# power_supply.net
KiCad netlist of a schematic drawn in Altium Designer
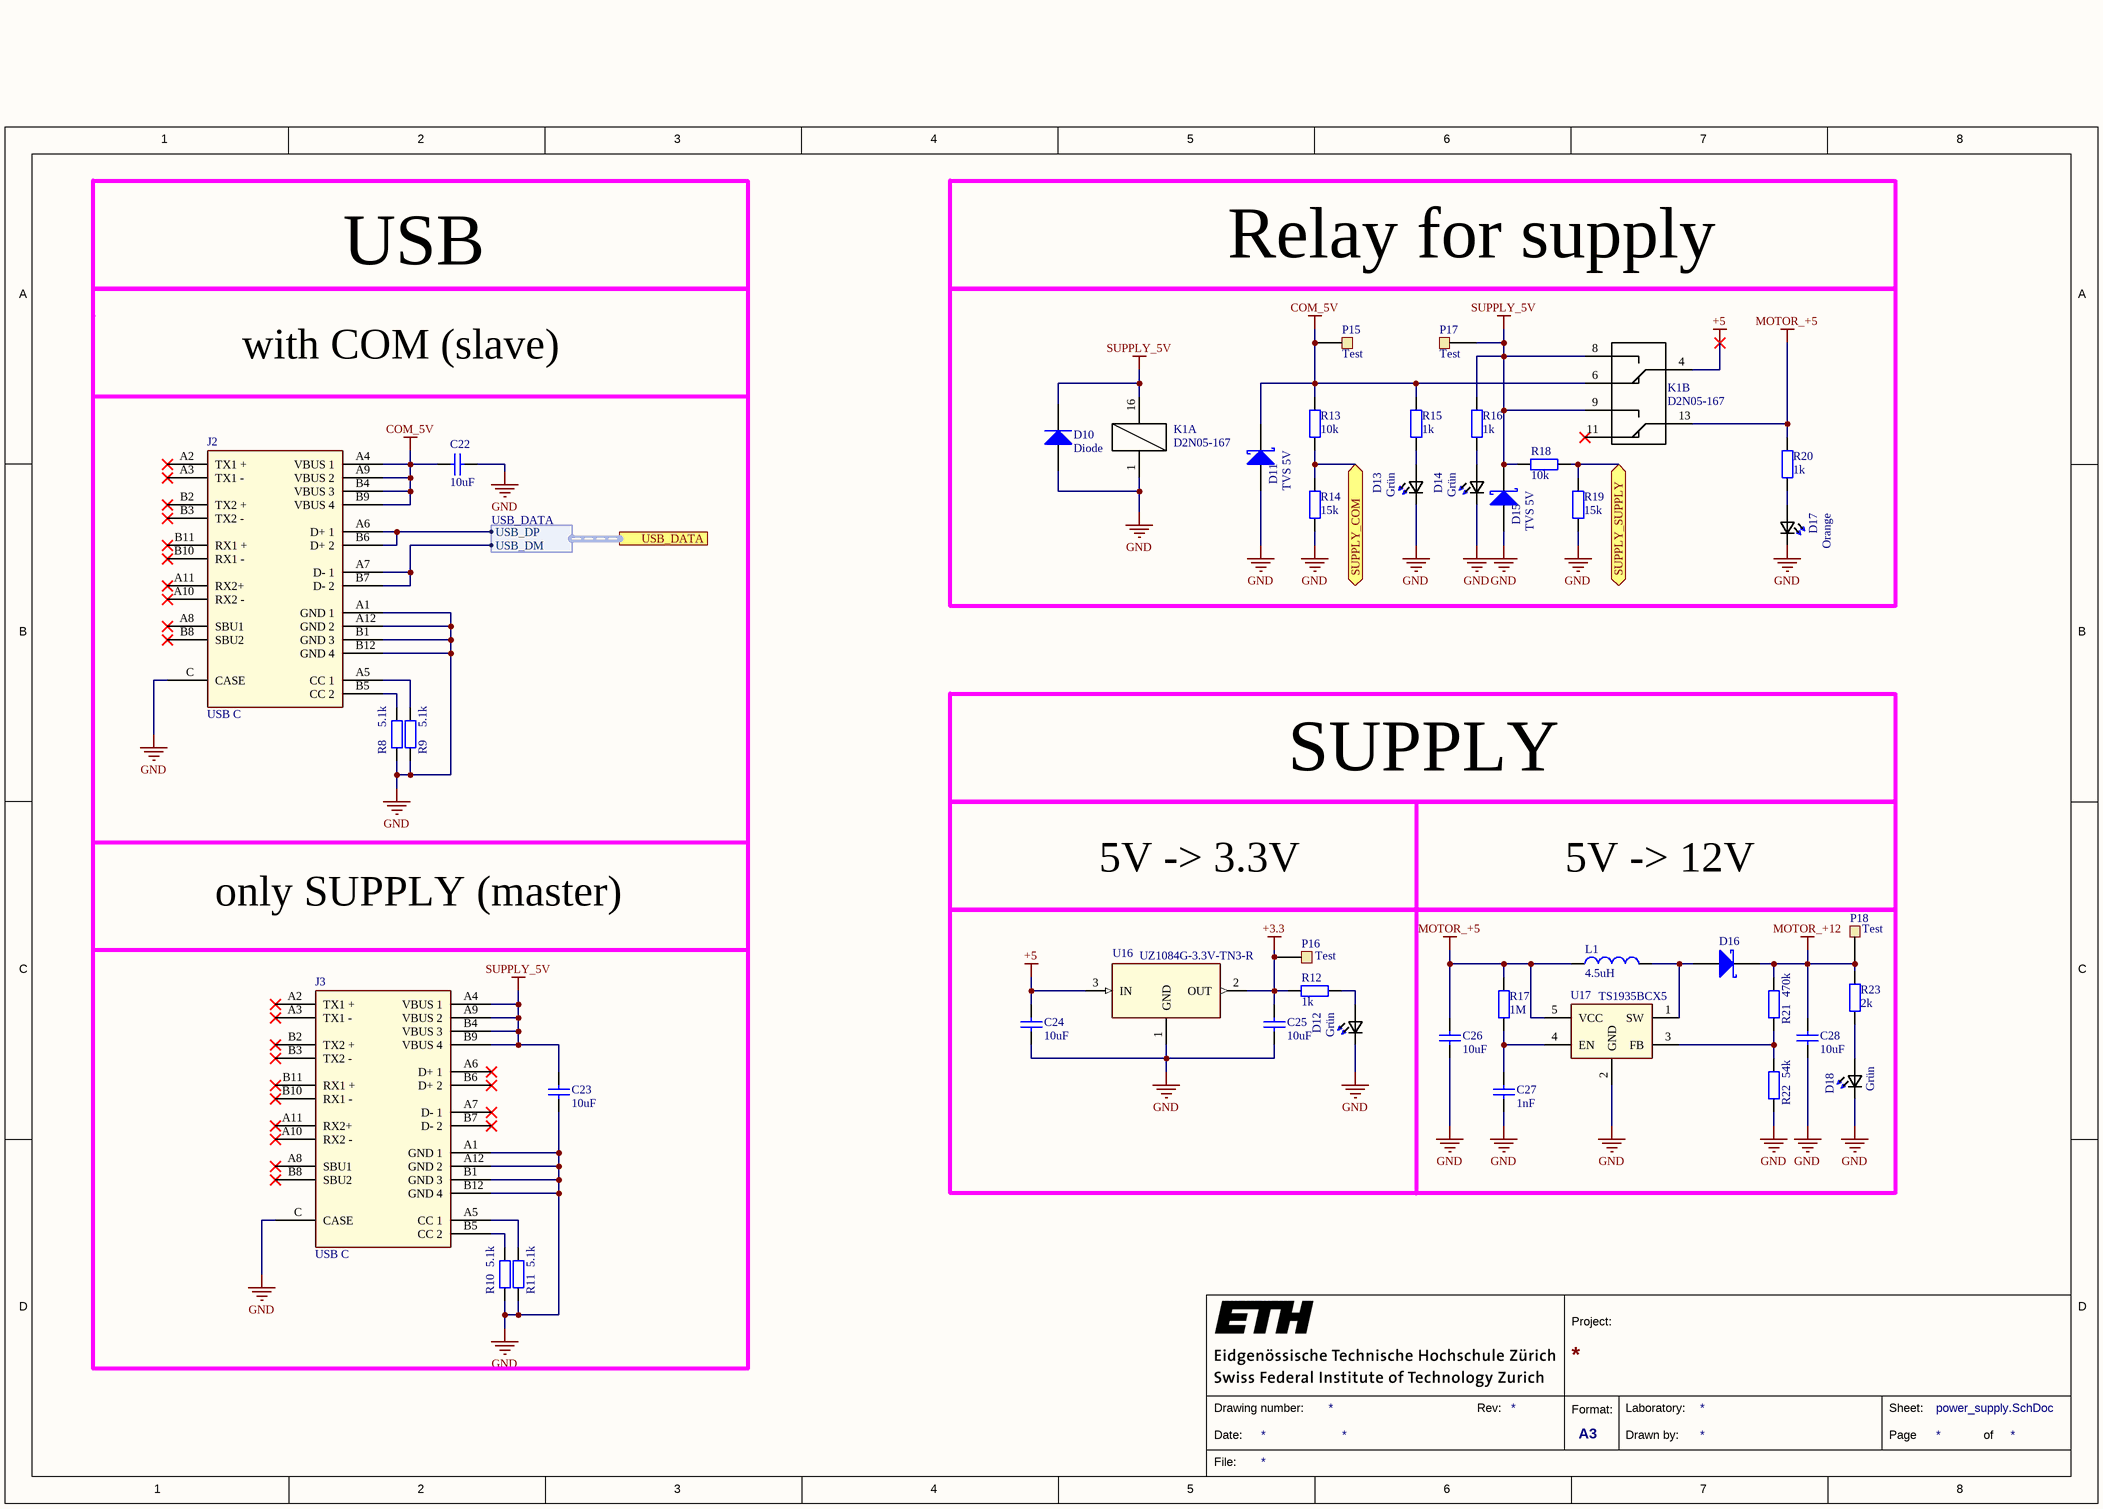
[diagram p0: power_supply.SchDoc]

(export (version "E")
  (design (tool "Eeschema 10.0.6"))
  (components
    (comp (ref "C22")
      (value "10uF")
      (footprint "CAP_0603i_1608m -L")
      (description "capacitor")
      (libsource (lib "IDSC std generic parts") (part "Cap"))
    )
    (comp (ref "C23")
      (value "10uF")
      (footprint "CAP_0603i_1608m -L")
      (description "capacitor")
      (libsource (lib "IDSC std generic parts") (part "Cap"))
    )
    (comp (ref "C24")
      (value "10uF")
      (footprint "CAP_0603i_1608m -L")
      (description "capacitor")
      (libsource (lib "IDSC std generic parts") (part "Cap"))
    )
    (comp (ref "C25")
      (value "10uF")
      (footprint "CAP_0603i_1608m -L")
      (description "capacitor")
      (libsource (lib "IDSC std generic parts") (part "Cap"))
    )
    (comp (ref "C26")
      (value "10uF")
      (footprint "CAP_0603i_1608m -L")
      (description "capacitor")
      (libsource (lib "IDSC std generic parts") (part "Cap"))
    )
    (comp (ref "C27")
      (value "1nF")
      (footprint "CAP_0402i_1005m -N")
      (description "capacitor")
      (libsource (lib "IDSC std generic parts") (part "Cap"))
    )
    (comp (ref "C28")
      (value "10uF")
      (footprint "CAP_0603i_1608m -L")
      (description "capacitor")
      (libsource (lib "IDSC std generic parts") (part "Cap"))
    )
    (comp (ref "D10")
      (value "Diode")
      (footprint "SOD-323-N")
      (description "Default Diode")
      (libsource (lib "IDSC std generic parts") (part "Diode"))
    )
    (comp (ref "D11")
      (value "TVS 5V")
      (footprint "SOD123")
      (description "TVS Diode")
      (libsource (lib "IDSC std generic parts") (part "Diode  Schottky"))
    )
    (comp (ref "D12")
      (value "Grün")
      (footprint "*0603")
      (description "LED; SMD; 0603; gr黱; 35mcd; 1.6x0.8x0.55mm; 130掳; 2梅2.V; 20mA")
      (fields (field (name "MP") "LTST-C191KGKT") (field (name "DIGI-KEY_PART_NUMBER") "160-1446-1-ND"))
      (libsource (lib "Funk") (part "LTST-C191KGKT"))
    )
    (comp (ref "D13")
      (value "Grün")
      (footprint "*0603")
      (description "LED; SMD; 0603; gr黱; 35mcd; 1.6x0.8x0.55mm; 130掳; 2梅2.V; 20mA")
      (fields (field (name "MP") "LTST-C191KGKT") (field (name "DIGI-KEY_PART_NUMBER") "160-1446-1-ND"))
      (libsource (lib "Funk") (part "LTST-C191KGKT"))
    )
    (comp (ref "D14")
      (value "Grün")
      (footprint "*0603")
      (description "LED; SMD; 0603; gr黱; 35mcd; 1.6x0.8x0.55mm; 130掳; 2梅2.V; 20mA")
      (fields (field (name "MP") "LTST-C191KGKT") (field (name "DIGI-KEY_PART_NUMBER") "160-1446-1-ND"))
      (libsource (lib "Funk") (part "LTST-C191KGKT"))
    )
    (comp (ref "D15")
      (value "TVS 5V")
      (footprint "SOD123")
      (description "TVS Diode")
      (libsource (lib "IDSC std generic parts") (part "Diode  Schottky"))
    )
    (comp (ref "D16")
      (value "Diode  Schottky")
      (footprint "Diode SMA DO-214AC -N")
      (description "Schottky Diode")
      (libsource (lib "IDSC std generic parts") (part "Diode  Schottky"))
    )
    (comp (ref "D17")
      (value "Orange")
      (footprint "*0603")
      (description "LED; SMD; 0603; orange; 45-90mcd; 1.6x0.8x0.55mm; 130Â°; 2Ã·2.4V; 20mA")
      (fields (field (name "MP") "LTST-C191KFKT") (field (name "DIGI-KEY_PART_NUMBER") "160-1445-1-ND"))
      (libsource (lib "Funk") (part "LTST-C191KFKT"))
    )
    (comp (ref "D18")
      (value "Grün")
      (footprint "*0603")
      (description "LED; SMD; 0603; gr黱; 35mcd; 1.6x0.8x0.55mm; 130掳; 2梅2.V; 20mA")
      (fields (field (name "MP") "LTST-C191KGKT") (field (name "DIGI-KEY_PART_NUMBER") "160-1446-1-ND"))
      (libsource (lib "Funk") (part "LTST-C191KGKT"))
    )
    (comp (ref "J2") (value "USB C") (footprint "80211-1921") (libsource (lib "BMA_lib") (part "USB C")))
    (comp (ref "J3") (value "USB C") (footprint "80211-1921") (libsource (lib "BMA_lib") (part "USB C")))
    (comp (ref "K1")
      (value "D2N05-167")
      (footprint "D2N05-167")
      (libsource (lib "BMA_lib") (part "D2N05-167"))
    )
    (comp (ref "L1")
      (value "4.5uH")
      (footprint "IND_0603i_1608m -L")
      (description "Inductor")
      (libsource (lib "IDSC std generic parts") (part "Inductor"))
    )
    (comp (ref "P15")
      (value "Test")
      (footprint "PIN1")
      (description "Single Pad or Testpoint")
      (libsource (lib "") (part "Pad_2"))
    )
    (comp (ref "P16")
      (value "Test")
      (footprint "PIN1")
      (description "Single Pad or Testpoint")
      (libsource (lib "") (part "Pad_2"))
    )
    (comp (ref "P17")
      (value "Test")
      (footprint "PIN1")
      (description "Single Pad or Testpoint")
      (libsource (lib "") (part "Pad_1"))
    )
    (comp (ref "P18")
      (value "Test")
      (footprint "PIN1")
      (description "Single Pad or Testpoint")
      (libsource (lib "IDSC std connectors") (part "Pad"))
    )
    (comp (ref "R8")
      (value "5.1k")
      (footprint "RES_0603i_1608m -N")
      (description "Resistor")
      (libsource (lib "") (part "Res_1"))
    )
    (comp (ref "R9") (value "5.1k") (footprint "RES_0603i_1608m -N") (libsource (lib "") (part "Res_1")))
    (comp (ref "R10")
      (value "5.1k")
      (footprint "RES_0603i_1608m -N")
      (description "Resistor")
      (libsource (lib "") (part "Res_1"))
    )
    (comp (ref "R11") (value "5.1k") (footprint "RES_0603i_1608m -N") (libsource (lib "") (part "Res_1")))
    (comp (ref "R12")
      (value "1k")
      (footprint "RES_0603i_1608m -N")
      (description "Resistor")
      (libsource (lib "") (part "Res_1"))
    )
    (comp (ref "R13")
      (value "10k")
      (footprint "RES_0603i_1608m -N")
      (libsource (lib "IDSC std generic parts") (part "Res"))
    )
    (comp (ref "R14")
      (value "15k")
      (footprint "RES_0603i_1608m -N")
      (libsource (lib "IDSC std generic parts") (part "Res"))
    )
    (comp (ref "R15")
      (value "1k")
      (footprint "RES_0603i_1608m -N")
      (description "Resistor")
      (libsource (lib "") (part "Res_2"))
    )
    (comp (ref "R16")
      (value "1k")
      (footprint "RES_0603i_1608m -N")
      (description "Resistor")
      (libsource (lib "") (part "Res_2"))
    )
    (comp (ref "R17") (value "1M") (footprint "RES_0603i_1608m -N") (libsource (lib "") (part "Res_1")))
    (comp (ref "R18") (value "10k") (footprint "RES_0603i_1608m -N") (libsource (lib "") (part "Res_2")))
    (comp (ref "R19")
      (value "15k")
      (footprint "RES_0603i_1608m -N")
      (libsource (lib "IDSC std generic parts") (part "Res"))
    )
    (comp (ref "R20")
      (value "1k")
      (footprint "RES_0603i_1608m -N")
      (description "Resistor")
      (libsource (lib "") (part "Res_2"))
    )
    (comp (ref "R21") (value "470k") (footprint "RES_0603i_1608m -N") (libsource (lib "") (part "Res_1")))
    (comp (ref "R22") (value "54k") (footprint "RES_0603i_1608m -N") (libsource (lib "") (part "Res_1")))
    (comp (ref "R23")
      (value "2k")
      (footprint "RES_0603i_1608m -N")
      (description "Resistor")
      (libsource (lib "") (part "Res_2"))
    )
    (comp (ref "U16")
      (value "UZ1084G-3.3V-TN3-R")
      (footprint "TO-252-2")
      (description "LINEAR VOLTAGE REGULATORS TO-252-2(DPAK) ROHS")
      (fields (field (name "MF") "Diodes Inc.") (field (name "MP") "AZ1117D-3.3TRE1"))
      (libsource (lib "BMA_lib") (part "UZ1084G-3.3V-TN3-R"))
    )
    (comp (ref "U17")
      (value "TS1935BCX5")
      (footprint "*SOT95P285X145-5N")
      (description "TS1935BCX5 Boost-Schaltregler Adj 1,9A 2,6-5,5Vi SOT23-5")
      (libsource (lib "BMA_lib") (part "TS1935BCX5"))
    )
  )
  (nets
    (net (code "2") (name "+3.3") (class "Default")
      (node (ref "C25") (pin "2") (pinfunction "2_2") (pintype "passive"))
      (node (ref "P16") (pin "1") (pinfunction "1_1") (pintype "passive"))
      (node (ref "R12") (pin "2") (pinfunction "2_2") (pintype "passive"))
      (node (ref "U16") (pin "2") (pinfunction "OUT_2") (pintype "output"))
    )
    (net (code "3") (name "+5") (class "Default")
      (node (ref "C24") (pin "2") (pinfunction "2_2") (pintype "passive"))
      (node (ref "K1") (pin "4") (pinfunction "4_4") (pintype "passive"))
      (node (ref "U16") (pin "3") (pinfunction "IN_3") (pintype "input"))
    )
    (net (code "4") (name "/SUPPLY_COM") (class "Default")
      (node (ref "R13") (pin "1") (pinfunction "1_1") (pintype "passive"))
      (node (ref "R14") (pin "2") (pinfunction "2_2") (pintype "passive"))
    )
    (net (code "5") (name "/SUPPLY_SUPPLY") (class "Default")
      (node (ref "R18") (pin "2") (pinfunction "2_2") (pintype "passive"))
      (node (ref "R19") (pin "2") (pinfunction "2_2") (pintype "passive"))
    )
    (net (code "7") (name "COM_5V") (class "Default")
      (node (ref "C22") (pin "2") (pinfunction "2_2") (pintype "passive"))
      (node (ref "D11") (pin "2") (pinfunction "K_2") (pintype "passive"))
      (node (ref "J2") (pin "A4") (pinfunction "VBUS_1_A4") (pintype "passive"))
      (node (ref "J2") (pin "A9") (pinfunction "VBUS_2_A9") (pintype "passive"))
      (node (ref "J2") (pin "B4") (pinfunction "VBUS_3_B4") (pintype "passive"))
      (node (ref "J2") (pin "B9") (pinfunction "VBUS_4_B9") (pintype "passive"))
      (node (ref "K1") (pin "6") (pinfunction "6_6") (pintype "passive"))
      (node (ref "P15") (pin "1") (pinfunction "1_1") (pintype "passive"))
      (node (ref "R13") (pin "2") (pinfunction "2_2") (pintype "passive"))
      (node (ref "R15") (pin "2") (pinfunction "2_2") (pintype "passive"))
    )
    (net (code "8") (name "GND") (class "Default")
      (node (ref "C22") (pin "1") (pinfunction "1_1") (pintype "passive"))
      (node (ref "C23") (pin "2") (pinfunction "2_2") (pintype "passive"))
      (node (ref "C24") (pin "1") (pinfunction "1_1") (pintype "passive"))
      (node (ref "C25") (pin "1") (pinfunction "1_1") (pintype "passive"))
      (node (ref "C26") (pin "1") (pinfunction "1_1") (pintype "passive"))
      (node (ref "C27") (pin "1") (pinfunction "1_1") (pintype "passive"))
      (node (ref "C28") (pin "1") (pinfunction "1_1") (pintype "passive"))
      (node (ref "D10") (pin "1") (pinfunction "A_1") (pintype "passive"))
      (node (ref "D11") (pin "1") (pinfunction "A_1") (pintype "passive"))
      (node (ref "D12") (pin "1") (pinfunction "K2_1") (pintype "passive"))
      (node (ref "D13") (pin "1") (pinfunction "K2_1") (pintype "passive"))
      (node (ref "D14") (pin "1") (pinfunction "K2_1") (pintype "passive"))
      (node (ref "D15") (pin "1") (pinfunction "A_1") (pintype "passive"))
      (node (ref "D17") (pin "1") (pinfunction "K2_1") (pintype "passive"))
      (node (ref "D18") (pin "1") (pinfunction "K2_1") (pintype "passive"))
      (node (ref "J2") (pin "A1") (pinfunction "GND_1_A1") (pintype "passive"))
      (node (ref "J2") (pin "A12") (pinfunction "GND_2_A12") (pintype "passive"))
      (node (ref "J2") (pin "B1") (pinfunction "GND_3_B1") (pintype "passive"))
      (node (ref "J2") (pin "B12") (pinfunction "GND_4_B12") (pintype "passive"))
      (node (ref "J2") (pin "C") (pinfunction "CASE_C") (pintype "passive"))
      (node (ref "J3") (pin "A1") (pinfunction "GND_1_A1") (pintype "passive"))
      (node (ref "J3") (pin "A12") (pinfunction "GND_2_A12") (pintype "passive"))
      (node (ref "J3") (pin "B1") (pinfunction "GND_3_B1") (pintype "passive"))
      (node (ref "J3") (pin "B12") (pinfunction "GND_4_B12") (pintype "passive"))
      (node (ref "J3") (pin "C") (pinfunction "CASE_C") (pintype "passive"))
      (node (ref "K1") (pin "1") (pinfunction "7_1") (pintype "passive"))
      (node (ref "R10") (pin "2") (pinfunction "2_2") (pintype "passive"))
      (node (ref "R11") (pin "2") (pinfunction "2_2") (pintype "passive"))
      (node (ref "R14") (pin "1") (pinfunction "1_1") (pintype "passive"))
      (node (ref "R19") (pin "1") (pinfunction "1_1") (pintype "passive"))
      (node (ref "R22") (pin "2") (pinfunction "2_2") (pintype "passive"))
      (node (ref "R8") (pin "2") (pinfunction "2_2") (pintype "passive"))
      (node (ref "R9") (pin "2") (pinfunction "2_2") (pintype "passive"))
      (node (ref "U16") (pin "1") (pinfunction "GND_1") (pintype "power_in"))
      (node (ref "U17") (pin "2") (pinfunction "GND_2") (pintype "passive"))
    )
    (net (code "9") (name "MOTOR_+5") (class "Default")
      (node (ref "C26") (pin "2") (pinfunction "2_2") (pintype "passive"))
      (node (ref "K1") (pin "13") (pinfunction "13_13") (pintype "passive"))
      (node (ref "L1") (pin "1") (pinfunction "1_1") (pintype "passive"))
      (node (ref "R17") (pin "1") (pinfunction "1_1") (pintype "passive"))
      (node (ref "R20") (pin "2") (pinfunction "2_2") (pintype "passive"))
      (node (ref "U17") (pin "5") (pinfunction "VCC_5") (pintype "passive"))
    )
    (net (code "10") (name "MOTOR_+12") (class "Default")
      (node (ref "C28") (pin "2") (pinfunction "2_2") (pintype "passive"))
      (node (ref "D16") (pin "2") (pinfunction "K_2") (pintype "passive"))
      (node (ref "P18") (pin "1") (pinfunction "1_1") (pintype "passive"))
      (node (ref "R21") (pin "1") (pinfunction "1_1") (pintype "passive"))
      (node (ref "R23") (pin "2") (pinfunction "2_2") (pintype "passive"))
    )
    (net (code "11") (name "Net-(D12-A2)") (class "Default")
      (node (ref "D12") (pin "2") (pinfunction "A2_2") (pintype "passive"))
      (node (ref "R12") (pin "1") (pinfunction "1_1") (pintype "passive"))
    )
    (net (code "12") (name "Net-(D13-A2)") (class "Default")
      (node (ref "D13") (pin "2") (pinfunction "A2_2") (pintype "passive"))
      (node (ref "R15") (pin "1") (pinfunction "1_1") (pintype "passive"))
    )
    (net (code "13") (name "Net-(D14-A2)") (class "Default")
      (node (ref "D14") (pin "2") (pinfunction "A2_2") (pintype "passive"))
      (node (ref "R16") (pin "1") (pinfunction "1_1") (pintype "passive"))
    )
    (net (code "14") (name "Net-(D16-A)") (class "Default")
      (node (ref "D16") (pin "1") (pinfunction "A_1") (pintype "passive"))
      (node (ref "L1") (pin "2") (pinfunction "2_2") (pintype "passive"))
      (node (ref "U17") (pin "1") (pinfunction "SW_1") (pintype "passive"))
    )
    (net (code "15") (name "Net-(D17-A2)") (class "Default")
      (node (ref "D17") (pin "2") (pinfunction "A2_2") (pintype "passive"))
      (node (ref "R20") (pin "1") (pinfunction "1_1") (pintype "passive"))
    )
    (net (code "16") (name "Net-(D18-A2)") (class "Default")
      (node (ref "D18") (pin "2") (pinfunction "A2_2") (pintype "passive"))
      (node (ref "R23") (pin "1") (pinfunction "1_1") (pintype "passive"))
    )
    (net (code "17") (name "Net-(J2-CC_1)") (class "Default")
      (node (ref "J2") (pin "A5") (pinfunction "CC_1_A5") (pintype "passive"))
      (node (ref "R9") (pin "1") (pinfunction "1_1") (pintype "passive"))
    )
    (net (code "18") (name "Net-(J2-CC_2)") (class "Default")
      (node (ref "J2") (pin "B5") (pinfunction "CC_2_B5") (pintype "passive"))
      (node (ref "R8") (pin "1") (pinfunction "1_1") (pintype "passive"))
    )
    (net (code "19") (name "Net-(J2-D+_1)") (class "Default")
      (node (ref "J2") (pin "A6") (pinfunction "D+_1_A6") (pintype "passive"))
      (node (ref "J2") (pin "B6") (pinfunction "D+_2_B6") (pintype "passive"))
    )
    (net (code "20") (name "Net-(J2-D-_1)") (class "Default")
      (node (ref "J2") (pin "A7") (pinfunction "D-_1_A7") (pintype "passive"))
      (node (ref "J2") (pin "B7") (pinfunction "D-_2_B7") (pintype "passive"))
    )
    (net (code "21") (name "Net-(J3-CC_1)") (class "Default")
      (node (ref "J3") (pin "A5") (pinfunction "CC_1_A5") (pintype "passive"))
      (node (ref "R11") (pin "1") (pinfunction "1_1") (pintype "passive"))
    )
    (net (code "22") (name "Net-(J3-CC_2)") (class "Default")
      (node (ref "J3") (pin "B5") (pinfunction "CC_2_B5") (pintype "passive"))
      (node (ref "R10") (pin "1") (pinfunction "1_1") (pintype "passive"))
    )
    (net (code "23") (name "Net-(U17-EN)") (class "Default")
      (node (ref "C27") (pin "2") (pinfunction "2_2") (pintype "passive"))
      (node (ref "R17") (pin "2") (pinfunction "2_2") (pintype "passive"))
      (node (ref "U17") (pin "4") (pinfunction "EN_4") (pintype "passive"))
    )
    (net (code "24") (name "Net-(U17-FB)") (class "Default")
      (node (ref "R21") (pin "2") (pinfunction "2_2") (pintype "passive"))
      (node (ref "R22") (pin "1") (pinfunction "1_1") (pintype "passive"))
      (node (ref "U17") (pin "3") (pinfunction "FB_3") (pintype "passive"))
    )
    (net (code "25") (name "SUPPLY_5V") (class "Default")
      (node (ref "C23") (pin "1") (pinfunction "1_1") (pintype "passive"))
      (node (ref "D10") (pin "2") (pinfunction "K_2") (pintype "passive"))
      (node (ref "D15") (pin "2") (pinfunction "K_2") (pintype "passive"))
      (node (ref "J3") (pin "A4") (pinfunction "VBUS_1_A4") (pintype "passive"))
      (node (ref "J3") (pin "A9") (pinfunction "VBUS_2_A9") (pintype "passive"))
      (node (ref "J3") (pin "B4") (pinfunction "VBUS_3_B4") (pintype "passive"))
      (node (ref "J3") (pin "B9") (pinfunction "VBUS_4_B9") (pintype "passive"))
      (node (ref "K1") (pin "16") (pinfunction "6_16") (pintype "passive"))
      (node (ref "K1") (pin "8") (pinfunction "8_8") (pintype "passive"))
      (node (ref "K1") (pin "9") (pinfunction "9_9") (pintype "passive"))
      (node (ref "P17") (pin "1") (pinfunction "1_1") (pintype "passive"))
      (node (ref "R16") (pin "2") (pinfunction "2_2") (pintype "passive"))
      (node (ref "R18") (pin "1") (pinfunction "1_1") (pintype "passive"))
    )
    (net (code "26") (name "unconnected-(J2-RX1_+-PadB11)") (class "Default")
      (node (ref "J2") (pin "B11") (pinfunction "RX1_+_B11") (pintype "passive+no_connect"))
    )
    (net (code "27") (name "unconnected-(J2-RX1_--PadB10)") (class "Default")
      (node (ref "J2") (pin "B10") (pinfunction "RX1_-_B10") (pintype "passive+no_connect"))
    )
    (net (code "28") (name "unconnected-(J2-RX2+-PadA11)") (class "Default")
      (node (ref "J2") (pin "A11") (pinfunction "RX2+_A11") (pintype "passive+no_connect"))
    )
    (net (code "29") (name "unconnected-(J2-RX2_--PadA10)") (class "Default")
      (node (ref "J2") (pin "A10") (pinfunction "RX2_-_A10") (pintype "passive+no_connect"))
    )
    (net (code "30") (name "unconnected-(J2-SBU1-PadA8)") (class "Default")
      (node (ref "J2") (pin "A8") (pinfunction "SBU1_A8") (pintype "passive+no_connect"))
    )
    (net (code "31") (name "unconnected-(J2-SBU2-PadB8)") (class "Default")
      (node (ref "J2") (pin "B8") (pinfunction "SBU2_B8") (pintype "passive+no_connect"))
    )
    (net (code "32") (name "unconnected-(J2-TX1_+-PadA2)") (class "Default")
      (node (ref "J2") (pin "A2") (pinfunction "TX1_+_A2") (pintype "passive+no_connect"))
    )
    (net (code "33") (name "unconnected-(J2-TX1_--PadA3)") (class "Default")
      (node (ref "J2") (pin "A3") (pinfunction "TX1_-_A3") (pintype "passive+no_connect"))
    )
    (net (code "34") (name "unconnected-(J2-TX2_+-PadB2)") (class "Default")
      (node (ref "J2") (pin "B2") (pinfunction "TX2_+_B2") (pintype "passive+no_connect"))
    )
    (net (code "35") (name "unconnected-(J2-TX2_--PadB3)") (class "Default")
      (node (ref "J2") (pin "B3") (pinfunction "TX2_-_B3") (pintype "passive+no_connect"))
    )
    (net (code "36") (name "unconnected-(J3-D+_1-PadA6)") (class "Default")
      (node (ref "J3") (pin "A6") (pinfunction "D+_1_A6") (pintype "passive+no_connect"))
    )
    (net (code "37") (name "unconnected-(J3-D+_2-PadB6)") (class "Default")
      (node (ref "J3") (pin "B6") (pinfunction "D+_2_B6") (pintype "passive+no_connect"))
    )
    (net (code "38") (name "unconnected-(J3-D-_1-PadA7)") (class "Default")
      (node (ref "J3") (pin "A7") (pinfunction "D-_1_A7") (pintype "passive+no_connect"))
    )
    (net (code "39") (name "unconnected-(J3-D-_2-PadB7)") (class "Default")
      (node (ref "J3") (pin "B7") (pinfunction "D-_2_B7") (pintype "passive+no_connect"))
    )
    (net (code "40") (name "unconnected-(J3-RX1_+-PadB11)") (class "Default")
      (node (ref "J3") (pin "B11") (pinfunction "RX1_+_B11") (pintype "passive+no_connect"))
    )
    (net (code "41") (name "unconnected-(J3-RX1_--PadB10)") (class "Default")
      (node (ref "J3") (pin "B10") (pinfunction "RX1_-_B10") (pintype "passive+no_connect"))
    )
    (net (code "42") (name "unconnected-(J3-RX2+-PadA11)") (class "Default")
      (node (ref "J3") (pin "A11") (pinfunction "RX2+_A11") (pintype "passive+no_connect"))
    )
    (net (code "43") (name "unconnected-(J3-RX2_--PadA10)") (class "Default")
      (node (ref "J3") (pin "A10") (pinfunction "RX2_-_A10") (pintype "passive+no_connect"))
    )
    (net (code "44") (name "unconnected-(J3-SBU1-PadA8)") (class "Default")
      (node (ref "J3") (pin "A8") (pinfunction "SBU1_A8") (pintype "passive+no_connect"))
    )
    (net (code "45") (name "unconnected-(J3-SBU2-PadB8)") (class "Default")
      (node (ref "J3") (pin "B8") (pinfunction "SBU2_B8") (pintype "passive+no_connect"))
    )
    (net (code "46") (name "unconnected-(J3-TX1_+-PadA2)") (class "Default")
      (node (ref "J3") (pin "A2") (pinfunction "TX1_+_A2") (pintype "passive+no_connect"))
    )
    (net (code "47") (name "unconnected-(J3-TX1_--PadA3)") (class "Default")
      (node (ref "J3") (pin "A3") (pinfunction "TX1_-_A3") (pintype "passive+no_connect"))
    )
    (net (code "48") (name "unconnected-(J3-TX2_+-PadB2)") (class "Default")
      (node (ref "J3") (pin "B2") (pinfunction "TX2_+_B2") (pintype "passive+no_connect"))
    )
    (net (code "49") (name "unconnected-(J3-TX2_--PadB3)") (class "Default")
      (node (ref "J3") (pin "B3") (pinfunction "TX2_-_B3") (pintype "passive+no_connect"))
    )
    (net (code "50") (name "unconnected-(K1-Pad11)") (class "Default")
      (node (ref "K1") (pin "11") (pinfunction "11_11") (pintype "passive+no_connect"))
    )
  )
)
